# untitled.net
KiCad netlist of a schematic drawn in EAGLE
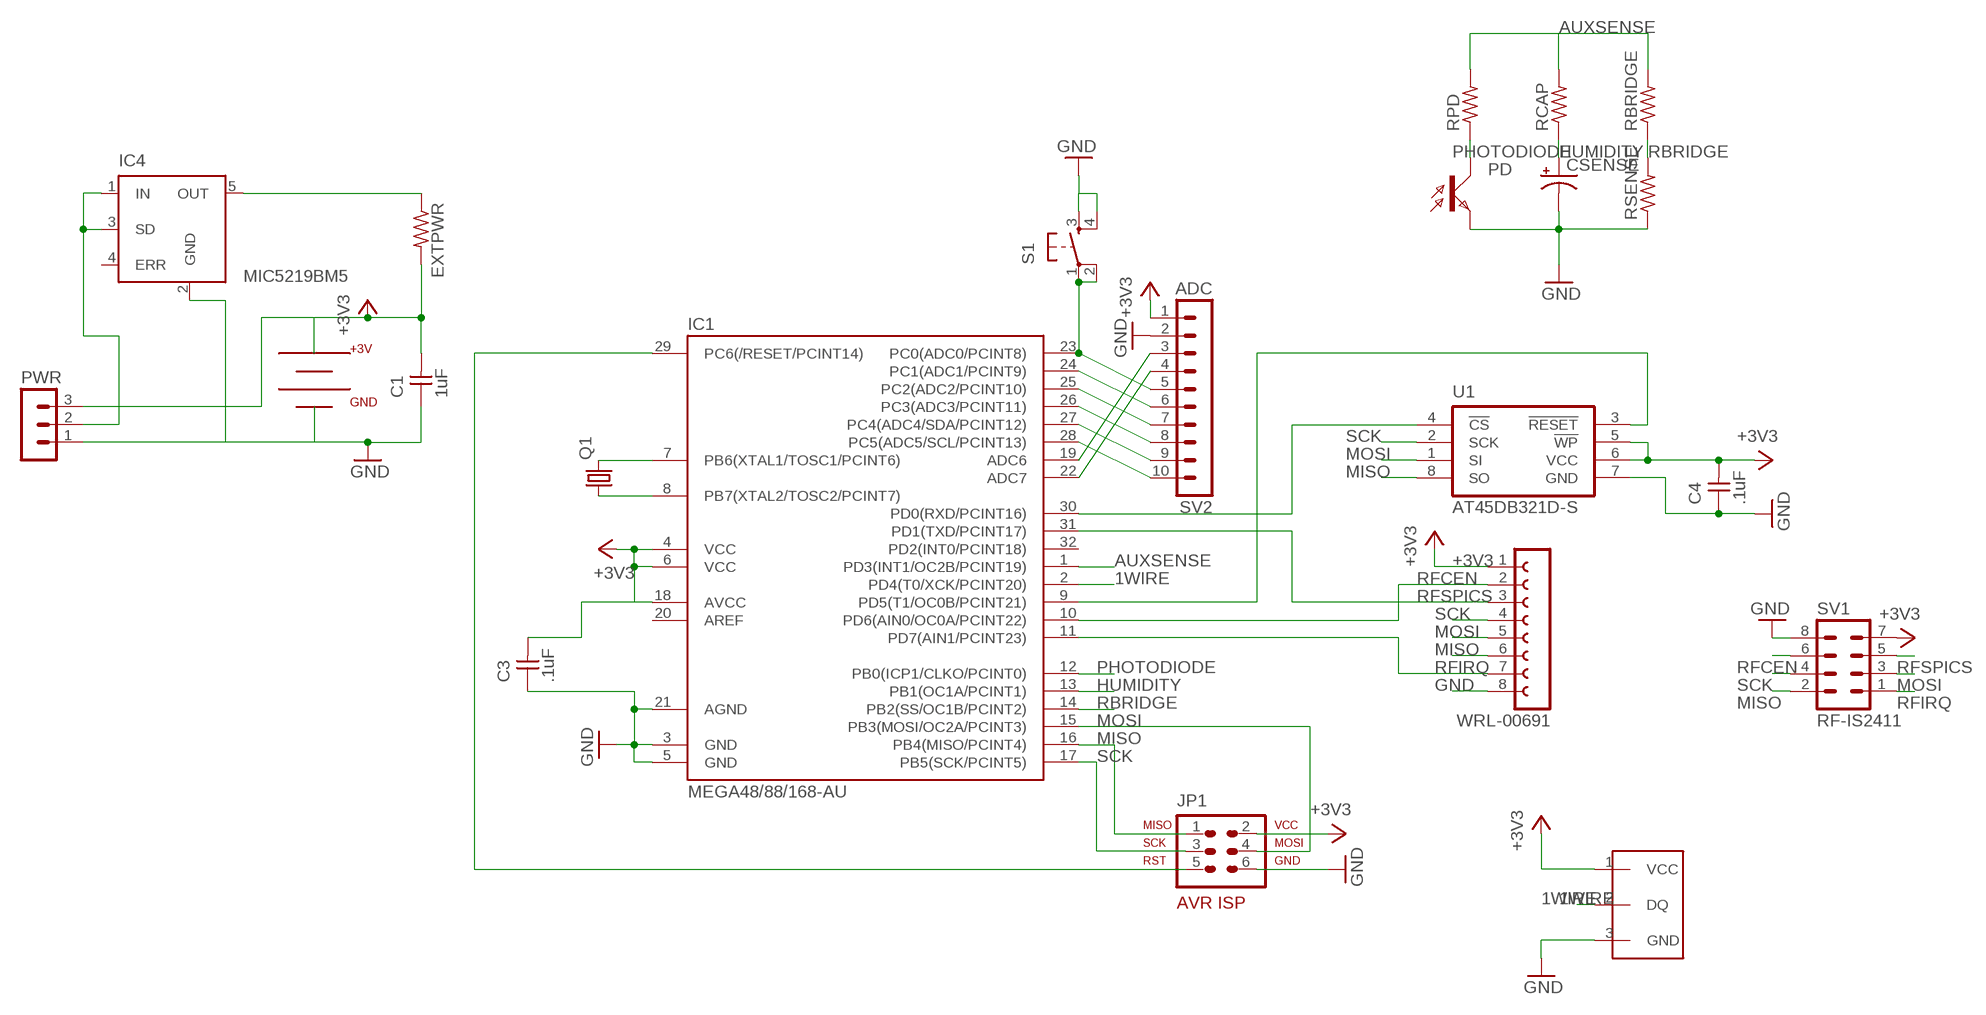
[diagram p0: schematic, sheet 1]

(export (version "E")
  (design (tool "Eeschema 10.0.6"))
  (components
    (comp (ref "C1")
      (value "1uF")
      (footprint "eagle-import:1206")
      (libsource (lib "eagle-import") (part "UNPOLARIZED_CAPACITOR1206"))
    )
    (comp (ref "C3")
      (value ".1uF")
      (footprint "eagle-import:1206")
      (libsource (lib "eagle-import") (part "UNPOLARIZED_CAPACITOR1206"))
    )
    (comp (ref "C4")
      (value ".1uF")
      (footprint "eagle-import:1206")
      (libsource (lib "eagle-import") (part "UNPOLARIZED_CAPACITOR1206"))
    )
    (comp (ref "CSENSE")
      (value "CPOL-USE5-8.5")
      (footprint "eagle-import:E5-8,5")
      (libsource (lib "eagle-import") (part "CPOL-USE5-8.5"))
    )
    (comp (ref "EXTPWR")
      (value "R-US_M0805")
      (footprint "eagle-import:M0805")
      (libsource (lib "eagle-import") (part "R-US_M0805"))
    )
    (comp (ref "IC1")
      (value "MEGA48/88/168-AU")
      (footprint "eagle-import:TQFP32-08")
      (libsource (lib "eagle-import") (part "MEGA48/88/168-AU"))
    )
    (comp (ref "IC4")
      (value "MIC5219BM5")
      (footprint "eagle-import:SOT23-5")
      (fields (field (name "MF") "ALTERA CORPORATION") (field (name "MPN") "MIC5219BM5 TR"))
      (libsource (lib "eagle-import") (part "MIC5219BM5"))
    )
    (comp (ref "JP1")
      (value "AVR-ISP")
      (footprint "eagle-import:AVR-ISP-6")
      (libsource (lib "eagle-import") (part "AVR-ISP-6VERT"))
    )
    (comp (ref "PD")
      (value "PHOTOTRANSISTOR5MM")
      (footprint "eagle-import:5MM")
      (libsource (lib "eagle-import") (part "PHOTOTRANSISTOR5MM"))
    )
    (comp (ref "PWR")
      (value "MA03-1")
      (footprint "eagle-import:MA03-1")
      (libsource (lib "eagle-import") (part "MA03-1"))
    )
    (comp (ref "Q1")
      (value "CRYSTALTC26H")
      (footprint "eagle-import:TC26H")
      (libsource (lib "eagle-import") (part "CRYSTALTC26H"))
    )
    (comp (ref "RBRIDGE")
      (value "RESISTOR1206")
      (footprint "eagle-import:1206")
      (libsource (lib "eagle-import") (part "RESISTOR1206"))
    )
    (comp (ref "RCAP")
      (value "RESISTOR1206")
      (footprint "eagle-import:1206")
      (libsource (lib "eagle-import") (part "RESISTOR1206"))
    )
    (comp (ref "RPD")
      (value "RESISTOR1206")
      (footprint "eagle-import:1206")
      (libsource (lib "eagle-import") (part "RESISTOR1206"))
    )
    (comp (ref "RSENSE")
      (value "R-US_0207/7")
      (footprint "eagle-import:0207_7")
      (libsource (lib "eagle-import") (part "R-US_0207/7"))
    )
    (comp (ref "S1")
      (value "6MM_SWITCH6MM_SWITCH")
      (footprint "eagle-import:6MM_SWITCH")
      (libsource (lib "eagle-import") (part "6MM_SWITCH6MM_SWITCH"))
    )
    (comp (ref "SV1")
      (value "RF-IS2411")
      (footprint "eagle-import:MA04-2")
      (libsource (lib "eagle-import") (part "MA04-2"))
    )
    (comp (ref "SV2")
      (value "ADC")
      (footprint "eagle-import:MA10-1")
      (libsource (lib "eagle-import") (part "MA10-1"))
    )
    (comp (ref "U$1")
      (value "BS-7BATTERYCLIP")
      (footprint "eagle-import:BS-7PACKAGE")
      (libsource (lib "eagle-import") (part "BS-7BATTERYCLIP"))
    )
    (comp (ref "U$2")
      (value "DS18S20")
      (footprint "eagle-import:TO92")
      (libsource (lib "eagle-import") (part "DS18S20"))
    )
    (comp (ref "U1")
      (value "AT45DB321D-S")
      (footprint "eagle-import:SO08-8S2")
      (libsource (lib "eagle-import") (part "AT45DB321D-S"))
    )
    (comp (ref "WRL-00691")
      (value "FE08-1")
      (footprint "eagle-import:FE08")
      (libsource (lib "eagle-import") (part "FE08-1"))
    )
  )
  (nets
    (net (code "1") (name "+3V3") (class "Default")
      (node (ref "C1") (pin "2") (pinfunction "2_2") (pintype "passive"))
      (node (ref "C3") (pin "2") (pinfunction "2_2") (pintype "passive"))
      (node (ref "C4") (pin "2") (pinfunction "2_2") (pintype "passive"))
      (node (ref "EXTPWR") (pin "2") (pinfunction "2_2") (pintype "passive"))
      (node (ref "IC1") (pin "18") (pinfunction "AVCC_18") (pintype "passive"))
      (node (ref "IC1") (pin "4") (pinfunction "VCC_4") (pintype "power_in"))
      (node (ref "IC1") (pin "6") (pinfunction "VCC_6") (pintype "power_in"))
      (node (ref "JP1") (pin "2") (pinfunction "2_2") (pintype "passive"))
      (node (ref "PWR") (pin "3") (pinfunction "3_3") (pintype "passive"))
      (node (ref "SV1") (pin "7") (pinfunction "7_7") (pintype "passive"))
      (node (ref "SV2") (pin "1") (pinfunction "1_1") (pintype "passive"))
      (node (ref "U$1") (pin "POS") (pinfunction "POS_POS") (pintype "bidirectional"))
      (node (ref "U$2") (pin "1") (pinfunction "VCC_1") (pintype "bidirectional"))
      (node (ref "U1") (pin "5") (pinfunction "~{WP}_5") (pintype "input"))
      (node (ref "U1") (pin "6") (pinfunction "VCC_6") (pintype "power_in"))
      (node (ref "WRL-00691") (pin "1") (pinfunction "1_1") (pintype "passive"))
    )
    (net (code "2") (name "/1WIRE") (class "Default")
      (node (ref "IC1") (pin "2") (pinfunction "PD4(T0/XCK/PCINT20)_2") (pintype "bidirectional"))
      (node (ref "U$2") (pin "2") (pinfunction "DQ_2") (pintype "bidirectional"))
    )
    (net (code "3") (name "/AUXSENSE") (class "Default")
      (node (ref "IC1") (pin "1") (pinfunction "PD3(INT1/OC2B/PCINT19)_1") (pintype "bidirectional"))
      (node (ref "RBRIDGE") (pin "2") (pinfunction "2_2") (pintype "passive"))
      (node (ref "RCAP") (pin "2") (pinfunction "2_2") (pintype "passive"))
      (node (ref "RPD") (pin "2") (pinfunction "2_2") (pintype "passive"))
    )
    (net (code "4") (name "/HUMIDITY") (class "Default")
      (node (ref "CSENSE") (pin "+") (pinfunction "+_+") (pintype "passive"))
      (node (ref "IC1") (pin "13") (pinfunction "PB1(OC1A/PCINT1)_13") (pintype "bidirectional"))
      (node (ref "RCAP") (pin "1") (pinfunction "1_1") (pintype "passive"))
    )
    (net (code "5") (name "/MISO") (class "Default")
      (node (ref "IC1") (pin "16") (pinfunction "PB4(MISO/PCINT4)_16") (pintype "bidirectional"))
      (node (ref "JP1") (pin "1") (pinfunction "1_1") (pintype "passive"))
      (node (ref "SV1") (pin "2") (pinfunction "2_2") (pintype "passive"))
      (node (ref "U1") (pin "8") (pinfunction "SO_8") (pintype "output"))
      (node (ref "WRL-00691") (pin "6") (pinfunction "6_6") (pintype "passive"))
    )
    (net (code "6") (name "/MOSI") (class "Default")
      (node (ref "IC1") (pin "15") (pinfunction "PB3(MOSI/OC2A/PCINT3)_15") (pintype "bidirectional"))
      (node (ref "JP1") (pin "4") (pinfunction "4_4") (pintype "passive"))
      (node (ref "SV1") (pin "3") (pinfunction "3_3") (pintype "passive"))
      (node (ref "U1") (pin "1") (pinfunction "SI_1") (pintype "input"))
      (node (ref "WRL-00691") (pin "5") (pinfunction "5_5") (pintype "passive"))
    )
    (net (code "7") (name "/PHOTODIODE") (class "Default")
      (node (ref "IC1") (pin "12") (pinfunction "PB0(ICP1/CLKO/PCINT0)_12") (pintype "bidirectional"))
      (node (ref "PD") (pin "IN") (pinfunction "C_IN") (pintype "passive"))
      (node (ref "RPD") (pin "1") (pinfunction "1_1") (pintype "passive"))
    )
    (net (code "8") (name "/RBRIDGE") (class "Default")
      (node (ref "IC1") (pin "14") (pinfunction "PB2(SS/OC1B/PCINT2)_14") (pintype "bidirectional"))
      (node (ref "RBRIDGE") (pin "1") (pinfunction "1_1") (pintype "passive"))
      (node (ref "RSENSE") (pin "2") (pinfunction "2_2") (pintype "passive"))
    )
    (net (code "9") (name "/RFCEN") (class "Default")
      (node (ref "IC1") (pin "10") (pinfunction "PD6(AIN0/OC0A/PCINT22)_10") (pintype "bidirectional"))
      (node (ref "SV1") (pin "6") (pinfunction "6_6") (pintype "passive"))
      (node (ref "WRL-00691") (pin "2") (pinfunction "2_2") (pintype "passive"))
    )
    (net (code "10") (name "/RFIRQ") (class "Default")
      (node (ref "IC1") (pin "11") (pinfunction "PD7(AIN1/PCINT23)_11") (pintype "bidirectional"))
      (node (ref "SV1") (pin "1") (pinfunction "1_1") (pintype "passive"))
      (node (ref "WRL-00691") (pin "7") (pinfunction "7_7") (pintype "passive"))
    )
    (net (code "11") (name "/RFSPICS") (class "Default")
      (node (ref "IC1") (pin "31") (pinfunction "PD1(TXD/PCINT17)_31") (pintype "bidirectional"))
      (node (ref "SV1") (pin "5") (pinfunction "5_5") (pintype "passive"))
      (node (ref "WRL-00691") (pin "3") (pinfunction "3_3") (pintype "passive"))
    )
    (net (code "12") (name "/SCK") (class "Default")
      (node (ref "IC1") (pin "17") (pinfunction "PB5(SCK/PCINT5)_17") (pintype "bidirectional"))
      (node (ref "JP1") (pin "3") (pinfunction "3_3") (pintype "passive"))
      (node (ref "SV1") (pin "4") (pinfunction "4_4") (pintype "passive"))
      (node (ref "U1") (pin "2") (pinfunction "SCK_2") (pintype "input"))
      (node (ref "WRL-00691") (pin "4") (pinfunction "4_4") (pintype "passive"))
    )
    (net (code "13") (name "GND") (class "Default")
      (node (ref "C1") (pin "1") (pinfunction "1_1") (pintype "passive"))
      (node (ref "C3") (pin "1") (pinfunction "1_1") (pintype "passive"))
      (node (ref "C4") (pin "1") (pinfunction "1_1") (pintype "passive"))
      (node (ref "CSENSE") (pin "-") (pinfunction "-_-") (pintype "passive"))
      (node (ref "IC1") (pin "21") (pinfunction "AGND_21") (pintype "power_in"))
      (node (ref "IC1") (pin "3") (pinfunction "GND_3") (pintype "power_in"))
      (node (ref "IC1") (pin "5") (pinfunction "GND_5") (pintype "power_in"))
      (node (ref "IC4") (pin "2") (pinfunction "GND_2") (pintype "power_in"))
      (node (ref "JP1") (pin "6") (pinfunction "6_6") (pintype "passive"))
      (node (ref "PD") (pin "OUT") (pinfunction "E_OUT") (pintype "passive"))
      (node (ref "PWR") (pin "1") (pinfunction "1_1") (pintype "passive"))
      (node (ref "RSENSE") (pin "1") (pinfunction "1_1") (pintype "passive"))
      (node (ref "S1") (pin "3") (pinfunction "S_3") (pintype "passive"))
      (node (ref "S1") (pin "4") (pinfunction "S1_4") (pintype "passive"))
      (node (ref "SV1") (pin "8") (pinfunction "8_8") (pintype "passive"))
      (node (ref "SV2") (pin "2") (pinfunction "2_2") (pintype "passive"))
      (node (ref "U$1") (pin "NEG") (pinfunction "NEG_NEG") (pintype "bidirectional"))
      (node (ref "U$2") (pin "3") (pinfunction "GND_3") (pintype "bidirectional"))
      (node (ref "U1") (pin "7") (pinfunction "GND_7") (pintype "power_in"))
      (node (ref "WRL-00691") (pin "8") (pinfunction "8_8") (pintype "passive"))
    )
    (net (code "14") (name "Net-(IC1-ADC6)") (class "Default")
      (node (ref "IC1") (pin "19") (pinfunction "ADC6_19") (pintype "passive"))
      (node (ref "SV2") (pin "3") (pinfunction "3_3") (pintype "passive"))
    )
    (net (code "15") (name "Net-(IC1-ADC7)") (class "Default")
      (node (ref "IC1") (pin "22") (pinfunction "ADC7_22") (pintype "passive"))
      (node (ref "SV2") (pin "4") (pinfunction "4_4") (pintype "passive"))
    )
    (net (code "16") (name "Net-(IC1-PB6(XTAL1{slash}TOSC1{slash}PCINT6))") (class "Default")
      (node (ref "IC1") (pin "7") (pinfunction "PB6(XTAL1/TOSC1/PCINT6)_7") (pintype "bidirectional"))
      (node (ref "Q1") (pin "2") (pinfunction "2_2") (pintype "passive"))
    )
    (net (code "17") (name "Net-(IC1-PB7(XTAL2{slash}TOSC2{slash}PCINT7))") (class "Default")
      (node (ref "IC1") (pin "8") (pinfunction "PB7(XTAL2/TOSC2/PCINT7)_8") (pintype "bidirectional"))
      (node (ref "Q1") (pin "1") (pinfunction "1_1") (pintype "passive"))
    )
    (net (code "18") (name "Net-(IC1-PC0(ADC0{slash}PCINT8))") (class "Default")
      (node (ref "IC1") (pin "23") (pinfunction "PC0(ADC0/PCINT8)_23") (pintype "bidirectional"))
      (node (ref "S1") (pin "1") (pinfunction "P_1") (pintype "passive"))
      (node (ref "S1") (pin "2") (pinfunction "P1_2") (pintype "passive"))
      (node (ref "SV2") (pin "5") (pinfunction "5_5") (pintype "passive"))
    )
    (net (code "19") (name "Net-(IC1-PC1(ADC1{slash}PCINT9))") (class "Default")
      (node (ref "IC1") (pin "24") (pinfunction "PC1(ADC1/PCINT9)_24") (pintype "bidirectional"))
      (node (ref "SV2") (pin "6") (pinfunction "6_6") (pintype "passive"))
    )
    (net (code "20") (name "Net-(IC1-PC2(ADC2{slash}PCINT10))") (class "Default")
      (node (ref "IC1") (pin "25") (pinfunction "PC2(ADC2/PCINT10)_25") (pintype "bidirectional"))
      (node (ref "SV2") (pin "7") (pinfunction "7_7") (pintype "passive"))
    )
    (net (code "21") (name "Net-(IC1-PC3(ADC3{slash}PCINT11))") (class "Default")
      (node (ref "IC1") (pin "26") (pinfunction "PC3(ADC3/PCINT11)_26") (pintype "bidirectional"))
      (node (ref "SV2") (pin "8") (pinfunction "8_8") (pintype "passive"))
    )
    (net (code "22") (name "Net-(IC1-PC4(ADC4{slash}SDA{slash}PCINT12))") (class "Default")
      (node (ref "IC1") (pin "27") (pinfunction "PC4(ADC4/SDA/PCINT12)_27") (pintype "bidirectional"))
      (node (ref "SV2") (pin "9") (pinfunction "9_9") (pintype "passive"))
    )
    (net (code "23") (name "Net-(IC1-PC5(ADC5{slash}SCL{slash}PCINT13))") (class "Default")
      (node (ref "IC1") (pin "28") (pinfunction "PC5(ADC5/SCL/PCINT13)_28") (pintype "bidirectional"))
      (node (ref "SV2") (pin "10") (pinfunction "10_10") (pintype "passive"))
    )
    (net (code "24") (name "Net-(IC1-PC6({slash}RESET{slash}PCINT14))") (class "Default")
      (node (ref "IC1") (pin "29") (pinfunction "PC6(/RESET/PCINT14)_29") (pintype "bidirectional"))
      (node (ref "JP1") (pin "5") (pinfunction "5_5") (pintype "passive"))
    )
    (net (code "25") (name "Net-(IC1-PD0(RXD{slash}PCINT16))") (class "Default")
      (node (ref "IC1") (pin "30") (pinfunction "PD0(RXD/PCINT16)_30") (pintype "bidirectional"))
      (node (ref "U1") (pin "4") (pinfunction "~{CS}_4") (pintype "input"))
    )
    (net (code "26") (name "Net-(IC1-PD5(T1{slash}OC0B{slash}PCINT21))") (class "Default")
      (node (ref "IC1") (pin "9") (pinfunction "PD5(T1/OC0B/PCINT21)_9") (pintype "bidirectional"))
      (node (ref "U1") (pin "3") (pinfunction "~{RESET}_3") (pintype "input"))
    )
    (net (code "27") (name "Net-(IC4-IN)") (class "Default")
      (node (ref "IC4") (pin "1") (pinfunction "IN_1") (pintype "input"))
      (node (ref "IC4") (pin "3") (pinfunction "SD_3") (pintype "input"))
      (node (ref "PWR") (pin "2") (pinfunction "2_2") (pintype "passive"))
    )
    (net (code "28") (name "Net-(IC4-OUT)") (class "Default")
      (node (ref "EXTPWR") (pin "1") (pinfunction "1_1") (pintype "passive"))
      (node (ref "IC4") (pin "5") (pinfunction "OUT_5") (pintype "output"))
    )
    (net (code "29") (name "unconnected-(IC1-AREF-Pad20)") (class "Default")
      (node (ref "IC1") (pin "20") (pinfunction "AREF_20") (pintype "passive"))
    )
    (net (code "30") (name "unconnected-(IC1-PD2(INT0{slash}PCINT18)-Pad32)") (class "Default")
      (node (ref "IC1") (pin "32") (pinfunction "PD2(INT0/PCINT18)_32") (pintype "bidirectional"))
    )
    (net (code "31") (name "unconnected-(IC4-ERR-Pad4)") (class "Default")
      (node (ref "IC4") (pin "4") (pinfunction "ERR_4") (pintype "passive"))
    )
  )
)
